# Featherwing_Version.net
KiCad netlist of a schematic drawn in EAGLE
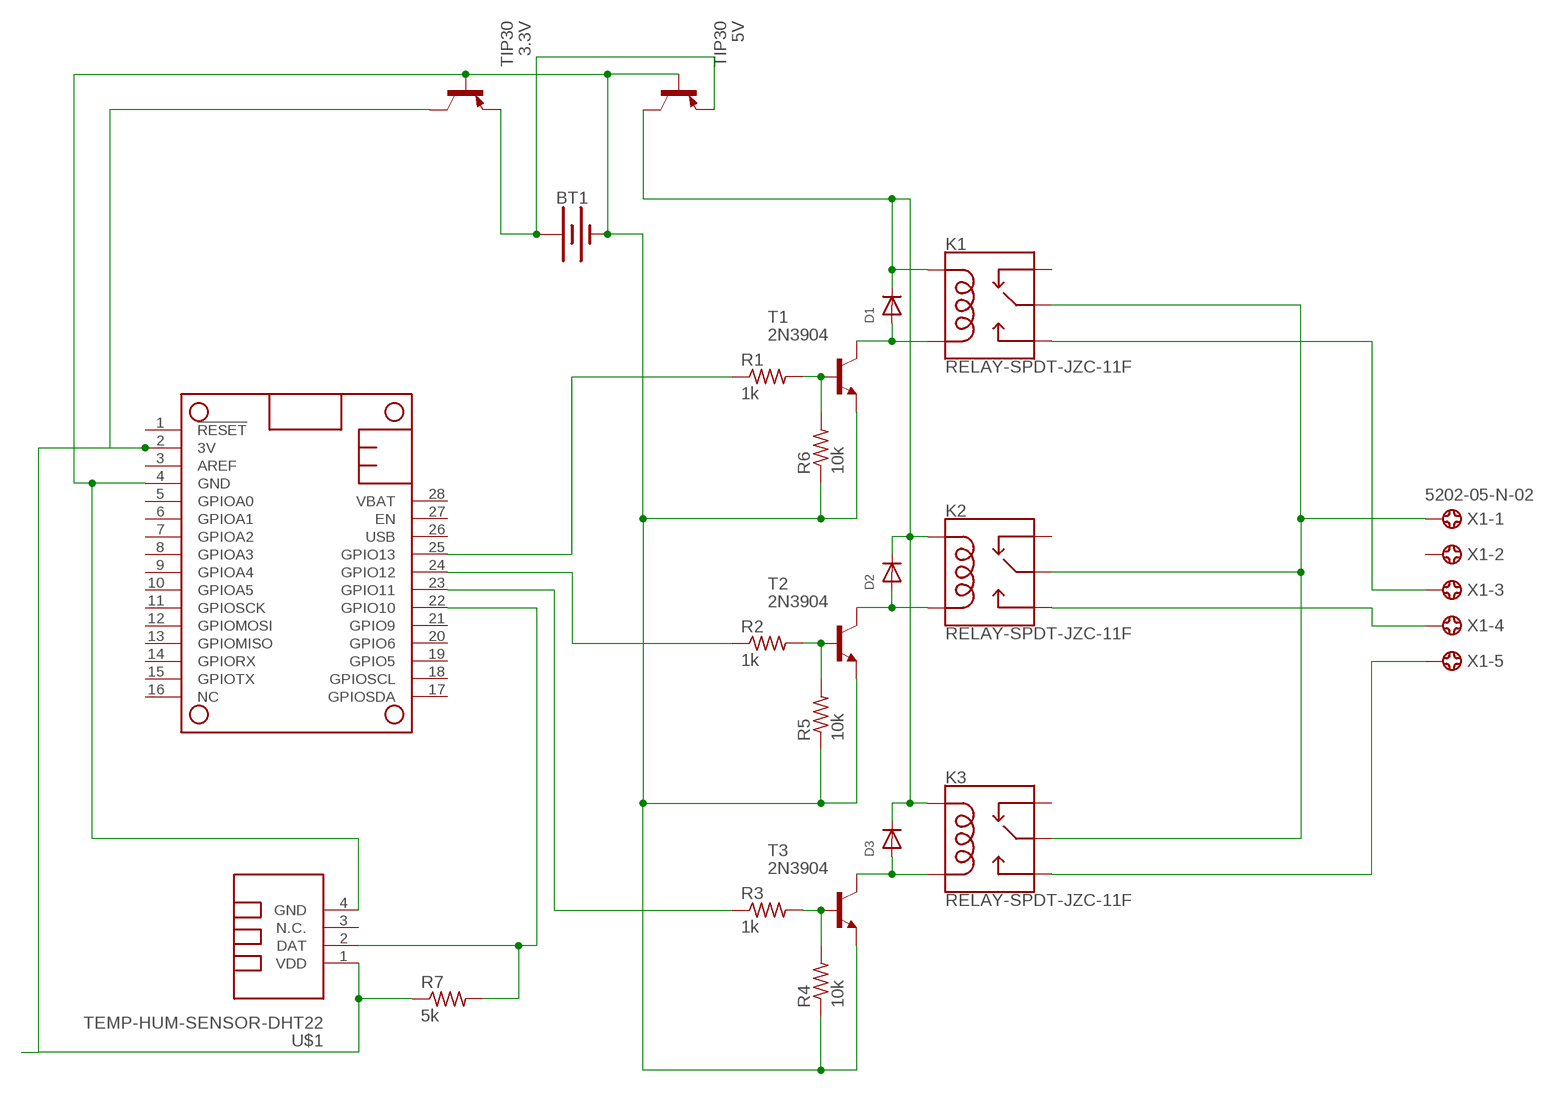
[diagram p0: schematic, sheet 1]

(export (version "E")
  (design (tool "Eeschema 10.0.6"))
  (components
    (comp (ref "3.3V")
      (value "TIP30")
      (footprint "eagle-import:TO220")
      (libsource (lib "eagle-import") (part "TIP30"))
    )
    (comp (ref "5V")
      (value "TIP30")
      (footprint "eagle-import:TO220")
      (libsource (lib "eagle-import") (part "TIP30"))
    )
    (comp (ref "BT1")
      (value "BATTERY-9V")
      (footprint "eagle-import:BATTCON_9V")
      (libsource (lib "eagle-import") (part "BATTERY-9V"))
    )
    (comp (ref "D1")
      (value "DIODEDO-1N4148")
      (footprint "eagle-import:DO-1N4148")
      (libsource (lib "eagle-import") (part "DIODEDO-1N4148"))
    )
    (comp (ref "D2")
      (value "DIODEDO-1N4148")
      (footprint "eagle-import:DO-1N4148")
      (libsource (lib "eagle-import") (part "DIODEDO-1N4148"))
    )
    (comp (ref "D3")
      (value "DIODEDO-1N4148")
      (footprint "eagle-import:DO-1N4148")
      (libsource (lib "eagle-import") (part "DIODEDO-1N4148"))
    )
    (comp (ref "K1")
      (value "RELAY-SPDT-JZC-11F")
      (footprint "eagle-import:RELAY-JZC")
      (libsource (lib "eagle-import") (part "RELAY-SPDT-JZC-11F"))
    )
    (comp (ref "K2")
      (value "RELAY-SPDT-JZC-11F")
      (footprint "eagle-import:RELAY-JZC")
      (libsource (lib "eagle-import") (part "RELAY-SPDT-JZC-11F"))
    )
    (comp (ref "K3")
      (value "RELAY-SPDT-JZC-11F")
      (footprint "eagle-import:RELAY-JZC")
      (libsource (lib "eagle-import") (part "RELAY-SPDT-JZC-11F"))
    )
    (comp (ref "MS2")
      (value "FEATHERWING")
      (footprint "eagle-import:FEATHERWING")
      (libsource (lib "eagle-import") (part "FEATHERWING"))
    )
    (comp (ref "R1")
      (value "1k")
      (footprint "eagle-import:0309_10")
      (libsource (lib "eagle-import") (part "R-US_0309/10"))
    )
    (comp (ref "R2")
      (value "1k")
      (footprint "eagle-import:0309_10")
      (libsource (lib "eagle-import") (part "R-US_0309/10"))
    )
    (comp (ref "R3")
      (value "1k")
      (footprint "eagle-import:0309_10")
      (libsource (lib "eagle-import") (part "R-US_0309/10"))
    )
    (comp (ref "R4")
      (value "10k")
      (footprint "eagle-import:0309_10")
      (libsource (lib "eagle-import") (part "R-US_0309/10"))
    )
    (comp (ref "R5")
      (value "10k")
      (footprint "eagle-import:0309_10")
      (libsource (lib "eagle-import") (part "R-US_0309/10"))
    )
    (comp (ref "R6")
      (value "10k")
      (footprint "eagle-import:0309_10")
      (libsource (lib "eagle-import") (part "R-US_0309/10"))
    )
    (comp (ref "R7")
      (value "5k")
      (footprint "eagle-import:0309_10")
      (libsource (lib "eagle-import") (part "R-US_0309/10"))
    )
    (comp (ref "T1")
      (value "2N3904")
      (footprint "eagle-import:TO92")
      (libsource (lib "eagle-import") (part "2N3904"))
    )
    (comp (ref "T2")
      (value "2N3904")
      (footprint "eagle-import:TO92")
      (libsource (lib "eagle-import") (part "2N3904"))
    )
    (comp (ref "T3")
      (value "2N3904")
      (footprint "eagle-import:TO92")
      (libsource (lib "eagle-import") (part "2N3904"))
    )
    (comp (ref "U$1")
      (value "TEMP-HUM-SENSOR-DHT22")
      (footprint "eagle-import:TEMP-HUM-SENSOR-DHT22")
      (libsource (lib "eagle-import") (part "TEMP-HUM-SENSOR-DHT22"))
    )
    (comp (ref "X1")
      (value "5202-05-N-02")
      (footprint "eagle-import:5202-05-N-02")
      (libsource (lib "eagle-import") (part "5202-05-N-02"))
    )
  )
  (nets
    (net (code "1") (name "/USB") (class "Default")
      (node (ref "MS2") (pin "26") (pinfunction "USB_26") (pintype "power_in"))
    )
    (net (code "2") (name "/VBAT") (class "Default")
      (node (ref "MS2") (pin "28") (pinfunction "VBAT_28") (pintype "power_in"))
    )
    (net (code "3") (name "Net-(3.3V-B)") (class "Default")
      (node (ref "3.3V") (pin "1") (pinfunction "B_1") (pintype "passive"))
      (node (ref "5V") (pin "1") (pinfunction "B_1") (pintype "passive"))
      (node (ref "BT1") (pin "-") (pinfunction "-_-") (pintype "power_in"))
      (node (ref "MS2") (pin "4") (pinfunction "GND_4") (pintype "power_in"))
      (node (ref "R4") (pin "1") (pinfunction "1_1") (pintype "passive"))
      (node (ref "R5") (pin "1") (pinfunction "1_1") (pintype "passive"))
      (node (ref "R6") (pin "1") (pinfunction "1_1") (pintype "passive"))
      (node (ref "T1") (pin "3") (pinfunction "E_3") (pintype "passive"))
      (node (ref "T2") (pin "3") (pinfunction "E_3") (pintype "passive"))
      (node (ref "T3") (pin "3") (pinfunction "E_3") (pintype "passive"))
      (node (ref "U$1") (pin "4") (pinfunction "GND_4") (pintype "power_in"))
    )
    (net (code "4") (name "Net-(3.3V-C)") (class "Default")
      (node (ref "3.3V") (pin "2") (pinfunction "C_2") (pintype "passive"))
      (node (ref "MS2") (pin "2") (pinfunction "3V_2") (pintype "power_in"))
      (node (ref "R7") (pin "1") (pinfunction "1_1") (pintype "passive"))
      (node (ref "U$1") (pin "1") (pinfunction "VDD_1") (pintype "power_in"))
    )
    (net (code "5") (name "Net-(3.3V-E)") (class "Default")
      (node (ref "3.3V") (pin "3") (pinfunction "E_3") (pintype "passive"))
      (node (ref "5V") (pin "3") (pinfunction "E_3") (pintype "passive"))
      (node (ref "BT1") (pin "+") (pinfunction "+_+") (pintype "power_in"))
    )
    (net (code "6") (name "Net-(5V-C)") (class "Default")
      (node (ref "5V") (pin "2") (pinfunction "C_2") (pintype "passive"))
      (node (ref "D1") (pin "C") (pinfunction "C_C") (pintype "passive"))
      (node (ref "D2") (pin "C") (pinfunction "C_C") (pintype "passive"))
      (node (ref "D3") (pin "C") (pinfunction "C_C") (pintype "passive"))
      (node (ref "K1") (pin "5") (pinfunction "COIL1_5") (pintype "bidirectional"))
      (node (ref "K2") (pin "5") (pinfunction "COIL1_5") (pintype "bidirectional"))
      (node (ref "K3") (pin "5") (pinfunction "COIL1_5") (pintype "bidirectional"))
    )
    (net (code "7") (name "Net-(K1-COIL2)") (class "Default")
      (node (ref "D1") (pin "A") (pinfunction "A_A") (pintype "passive"))
      (node (ref "K1") (pin "1") (pinfunction "COIL2_1") (pintype "bidirectional"))
      (node (ref "T1") (pin "1") (pinfunction "C_1") (pintype "passive"))
    )
    (net (code "8") (name "Net-(K1-MAIN)") (class "Default")
      (node (ref "K1") (pin "4") (pinfunction "MAIN_4") (pintype "bidirectional"))
      (node (ref "K2") (pin "4") (pinfunction "MAIN_4") (pintype "bidirectional"))
      (node (ref "K3") (pin "4") (pinfunction "MAIN_4") (pintype "bidirectional"))
      (node (ref "X1") (pin "1") (pinfunction "1_1") (pintype "passive"))
    )
    (net (code "9") (name "Net-(K1-NO)") (class "Default")
      (node (ref "K1") (pin "3") (pinfunction "NO_3") (pintype "bidirectional"))
      (node (ref "X1") (pin "3") (pinfunction "1_3") (pintype "passive"))
    )
    (net (code "10") (name "Net-(K2-COIL2)") (class "Default")
      (node (ref "D2") (pin "A") (pinfunction "A_A") (pintype "passive"))
      (node (ref "K2") (pin "1") (pinfunction "COIL2_1") (pintype "bidirectional"))
      (node (ref "T2") (pin "1") (pinfunction "C_1") (pintype "passive"))
    )
    (net (code "11") (name "Net-(K2-NO)") (class "Default")
      (node (ref "K2") (pin "3") (pinfunction "NO_3") (pintype "bidirectional"))
      (node (ref "X1") (pin "4") (pinfunction "1_4") (pintype "passive"))
    )
    (net (code "12") (name "Net-(K3-COIL2)") (class "Default")
      (node (ref "D3") (pin "A") (pinfunction "A_A") (pintype "passive"))
      (node (ref "K3") (pin "1") (pinfunction "COIL2_1") (pintype "bidirectional"))
      (node (ref "T3") (pin "1") (pinfunction "C_1") (pintype "passive"))
    )
    (net (code "13") (name "Net-(K3-NO)") (class "Default")
      (node (ref "K3") (pin "3") (pinfunction "NO_3") (pintype "bidirectional"))
      (node (ref "X1") (pin "5") (pinfunction "1_5") (pintype "passive"))
    )
    (net (code "14") (name "Net-(MS2-GPIO10)") (class "Default")
      (node (ref "MS2") (pin "22") (pinfunction "GPIO10_22") (pintype "bidirectional"))
      (node (ref "R7") (pin "2") (pinfunction "2_2") (pintype "passive"))
      (node (ref "U$1") (pin "2") (pinfunction "DAT_2") (pintype "bidirectional"))
    )
    (net (code "15") (name "Net-(MS2-GPIO11)") (class "Default")
      (node (ref "MS2") (pin "23") (pinfunction "GPIO11_23") (pintype "bidirectional"))
      (node (ref "R3") (pin "1") (pinfunction "1_1") (pintype "passive"))
    )
    (net (code "16") (name "Net-(MS2-GPIO12)") (class "Default")
      (node (ref "MS2") (pin "24") (pinfunction "GPIO12_24") (pintype "bidirectional"))
      (node (ref "R2") (pin "1") (pinfunction "1_1") (pintype "passive"))
    )
    (net (code "17") (name "Net-(MS2-GPIO13)") (class "Default")
      (node (ref "MS2") (pin "25") (pinfunction "GPIO13_25") (pintype "bidirectional"))
      (node (ref "R1") (pin "1") (pinfunction "1_1") (pintype "passive"))
    )
    (net (code "18") (name "Net-(T1-B)") (class "Default")
      (node (ref "R1") (pin "2") (pinfunction "2_2") (pintype "passive"))
      (node (ref "R6") (pin "2") (pinfunction "2_2") (pintype "passive"))
      (node (ref "T1") (pin "2") (pinfunction "B_2") (pintype "passive"))
    )
    (net (code "19") (name "Net-(T2-B)") (class "Default")
      (node (ref "R2") (pin "2") (pinfunction "2_2") (pintype "passive"))
      (node (ref "R5") (pin "2") (pinfunction "2_2") (pintype "passive"))
      (node (ref "T2") (pin "2") (pinfunction "B_2") (pintype "passive"))
    )
    (net (code "20") (name "Net-(T3-B)") (class "Default")
      (node (ref "R3") (pin "2") (pinfunction "2_2") (pintype "passive"))
      (node (ref "R4") (pin "2") (pinfunction "2_2") (pintype "passive"))
      (node (ref "T3") (pin "2") (pinfunction "B_2") (pintype "passive"))
    )
    (net (code "21") (name "unconnected-(K1-NC-Pad2)") (class "Default")
      (node (ref "K1") (pin "2") (pinfunction "NC_2") (pintype "bidirectional"))
    )
    (net (code "22") (name "unconnected-(K2-NC-Pad2)") (class "Default")
      (node (ref "K2") (pin "2") (pinfunction "NC_2") (pintype "bidirectional"))
    )
    (net (code "23") (name "unconnected-(K3-NC-Pad2)") (class "Default")
      (node (ref "K3") (pin "2") (pinfunction "NC_2") (pintype "bidirectional"))
    )
    (net (code "24") (name "unconnected-(MS2-AREF-Pad3)") (class "Default")
      (node (ref "MS2") (pin "3") (pinfunction "AREF_3") (pintype "passive"))
    )
    (net (code "25") (name "unconnected-(MS2-EN-Pad27)") (class "Default")
      (node (ref "MS2") (pin "27") (pinfunction "EN_27") (pintype "passive"))
    )
    (net (code "26") (name "unconnected-(MS2-GPIO5-Pad19)") (class "Default")
      (node (ref "MS2") (pin "19") (pinfunction "GPIO5_19") (pintype "bidirectional"))
    )
    (net (code "27") (name "unconnected-(MS2-GPIO6-Pad20)") (class "Default")
      (node (ref "MS2") (pin "20") (pinfunction "GPIO6_20") (pintype "bidirectional"))
    )
    (net (code "28") (name "unconnected-(MS2-GPIO9-Pad21)") (class "Default")
      (node (ref "MS2") (pin "21") (pinfunction "GPIO9_21") (pintype "bidirectional"))
    )
    (net (code "29") (name "unconnected-(MS2-GPIOA0-Pad5)") (class "Default")
      (node (ref "MS2") (pin "5") (pinfunction "GPIOA0_5") (pintype "bidirectional"))
    )
    (net (code "30") (name "unconnected-(MS2-GPIOA1-Pad6)") (class "Default")
      (node (ref "MS2") (pin "6") (pinfunction "GPIOA1_6") (pintype "bidirectional"))
    )
    (net (code "31") (name "unconnected-(MS2-GPIOA2-Pad7)") (class "Default")
      (node (ref "MS2") (pin "7") (pinfunction "GPIOA2_7") (pintype "bidirectional"))
    )
    (net (code "32") (name "unconnected-(MS2-GPIOA3-Pad8)") (class "Default")
      (node (ref "MS2") (pin "8") (pinfunction "GPIOA3_8") (pintype "bidirectional"))
    )
    (net (code "33") (name "unconnected-(MS2-GPIOA4-Pad9)") (class "Default")
      (node (ref "MS2") (pin "9") (pinfunction "GPIOA4_9") (pintype "bidirectional"))
    )
    (net (code "34") (name "unconnected-(MS2-GPIOA5-Pad10)") (class "Default")
      (node (ref "MS2") (pin "10") (pinfunction "GPIOA5_10") (pintype "bidirectional"))
    )
    (net (code "35") (name "unconnected-(MS2-GPIOMISO-Pad13)") (class "Default")
      (node (ref "MS2") (pin "13") (pinfunction "GPIOMISO_13") (pintype "bidirectional"))
    )
    (net (code "36") (name "unconnected-(MS2-GPIOMOSI-Pad12)") (class "Default")
      (node (ref "MS2") (pin "12") (pinfunction "GPIOMOSI_12") (pintype "bidirectional"))
    )
    (net (code "37") (name "unconnected-(MS2-GPIORX-Pad14)") (class "Default")
      (node (ref "MS2") (pin "14") (pinfunction "GPIORX_14") (pintype "bidirectional"))
    )
    (net (code "38") (name "unconnected-(MS2-GPIOSCK-Pad11)") (class "Default")
      (node (ref "MS2") (pin "11") (pinfunction "GPIOSCK_11") (pintype "bidirectional"))
    )
    (net (code "39") (name "unconnected-(MS2-GPIOSCL-Pad18)") (class "Default")
      (node (ref "MS2") (pin "18") (pinfunction "GPIOSCL_18") (pintype "bidirectional"))
    )
    (net (code "40") (name "unconnected-(MS2-GPIOSDA-Pad17)") (class "Default")
      (node (ref "MS2") (pin "17") (pinfunction "GPIOSDA_17") (pintype "bidirectional"))
    )
    (net (code "41") (name "unconnected-(MS2-GPIOTX-Pad15)") (class "Default")
      (node (ref "MS2") (pin "15") (pinfunction "GPIOTX_15") (pintype "bidirectional"))
    )
    (net (code "42") (name "unconnected-(MS2-NC-Pad16)") (class "Default")
      (node (ref "MS2") (pin "16") (pinfunction "NC_16") (pintype "passive"))
    )
    (net (code "43") (name "unconnected-(MS2-~{RESET}-Pad1)") (class "Default")
      (node (ref "MS2") (pin "1") (pinfunction "~{RESET}_1") (pintype "input"))
    )
    (net (code "44") (name "unconnected-(U$1-N.C.-Pad3)") (class "Default")
      (node (ref "U$1") (pin "3") (pinfunction "N.C._3") (pintype "passive"))
    )
    (net (code "45") (name "unconnected-(X1B-1-Pad2)") (class "Default")
      (node (ref "X1") (pin "2") (pinfunction "1_2") (pintype "passive"))
    )
  )
)
